# ir_serial_interface.net
KiCad netlist of a schematic drawn in EAGLE
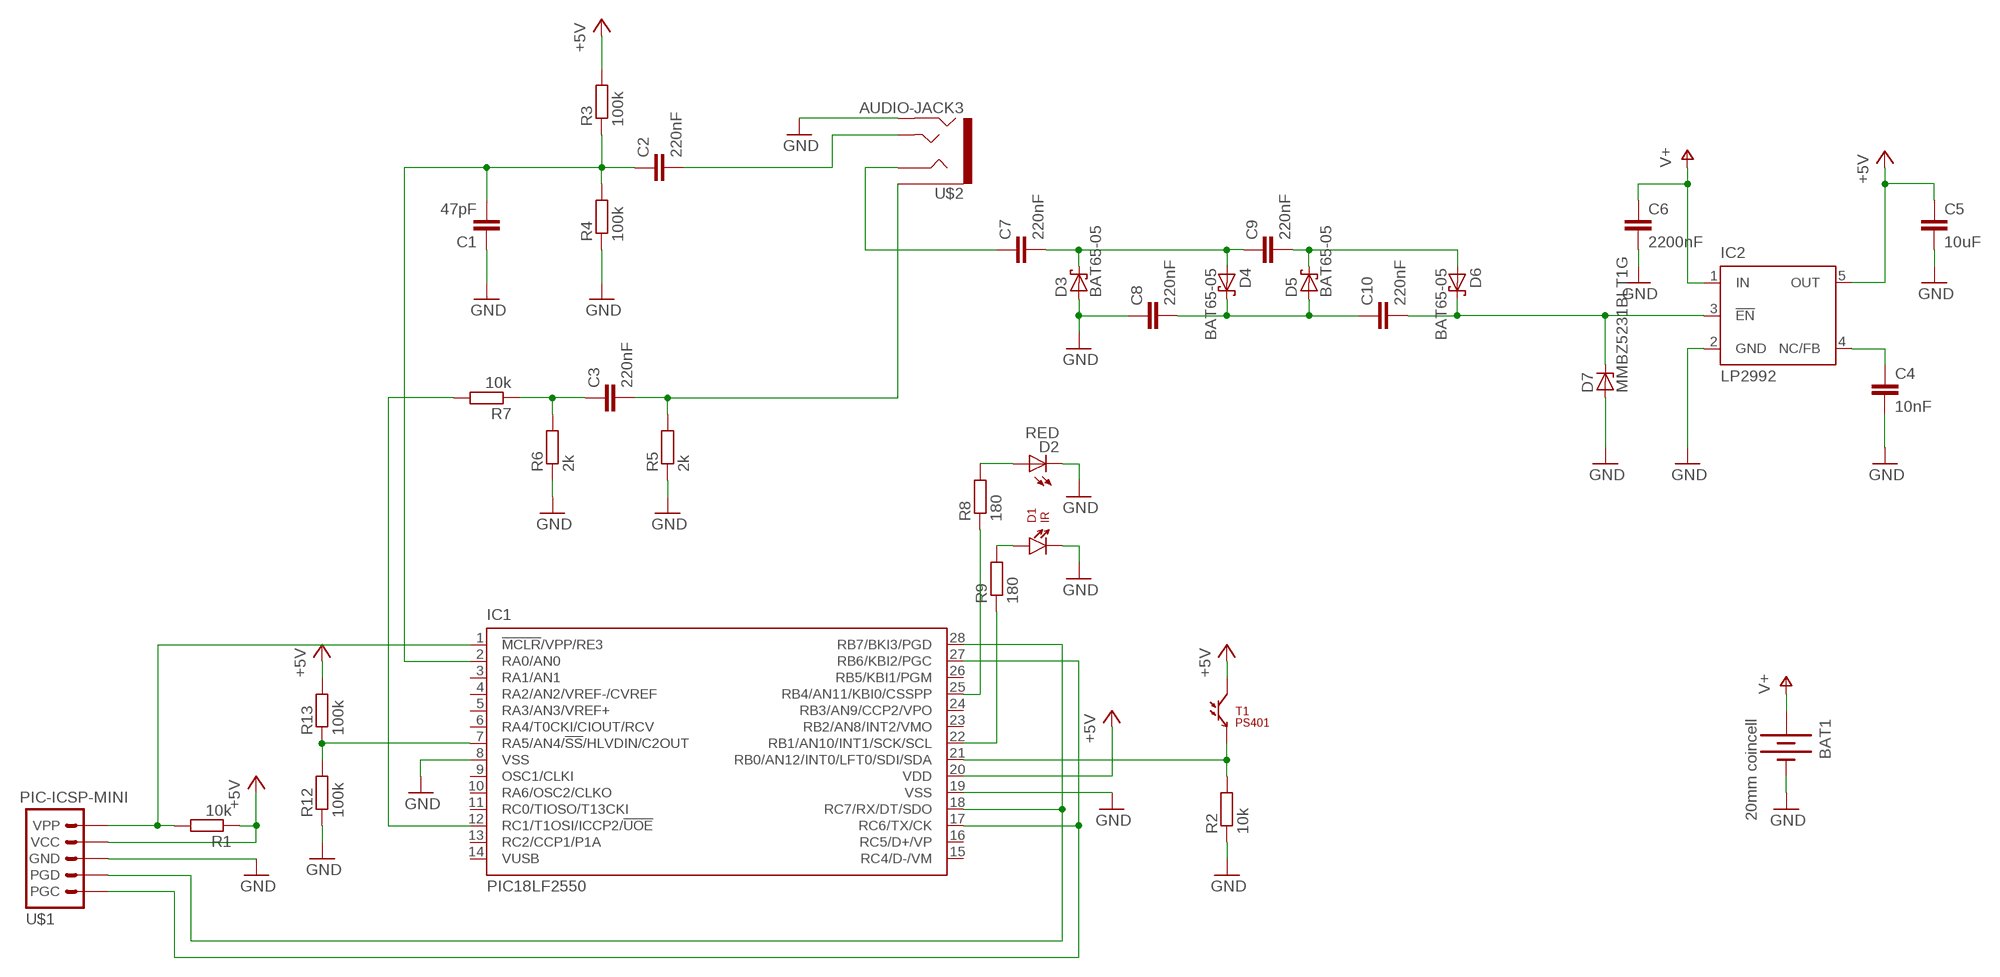
[diagram p0: schematic, sheet 1]

(export (version "E")
  (design (tool "Eeschema 10.0.6"))
  (components
    (comp (ref "BAT1")
      (value "20mm coincell")
      (footprint "eagle-import:BATTCOM_20MM_PTH")
      (libsource (lib "eagle-import") (part "BATTERY20PTH"))
    )
    (comp (ref "C1")
      (value "47pF")
      (footprint "eagle-import:0805")
      (libsource (lib "eagle-import") (part "CAP0805"))
    )
    (comp (ref "C2")
      (value "220nF")
      (footprint "eagle-import:0805")
      (libsource (lib "eagle-import") (part "CAP0805"))
    )
    (comp (ref "C3")
      (value "220nF")
      (footprint "eagle-import:0805")
      (libsource (lib "eagle-import") (part "CAP0805"))
    )
    (comp (ref "C4")
      (value "10nF")
      (footprint "eagle-import:C0805")
      (libsource (lib "eagle-import") (part "C-EUC0805"))
    )
    (comp (ref "C5")
      (value "10uF")
      (footprint "eagle-import:C0805")
      (libsource (lib "eagle-import") (part "C-EUC0805"))
    )
    (comp (ref "C6")
      (value "2200nF")
      (footprint "eagle-import:C0805")
      (libsource (lib "eagle-import") (part "C-EUC0805"))
    )
    (comp (ref "C7")
      (value "220nF")
      (footprint "eagle-import:C0805")
      (libsource (lib "eagle-import") (part "C-EUC0805"))
    )
    (comp (ref "C8")
      (value "220nF")
      (footprint "eagle-import:C0805")
      (libsource (lib "eagle-import") (part "C-EUC0805"))
    )
    (comp (ref "C9")
      (value "220nF")
      (footprint "eagle-import:C0805")
      (libsource (lib "eagle-import") (part "C-EUC0805"))
    )
    (comp (ref "C10")
      (value "220nF")
      (footprint "eagle-import:C0805")
      (libsource (lib "eagle-import") (part "C-EUC0805"))
    )
    (comp (ref "D1")
      (value "IR")
      (footprint "eagle-import:LTE-302")
      (libsource (lib "eagle-import") (part "LTE-302"))
    )
    (comp (ref "D2")
      (value "RED")
      (footprint "eagle-import:LED-1206")
      (libsource (lib "eagle-import") (part "LED-REDLILYPAD"))
    )
    (comp (ref "D3")
      (value "BAT65-05")
      (footprint "eagle-import:SOT23")
      (libsource (lib "eagle-import") (part "BAT54"))
    )
    (comp (ref "D4")
      (value "BAT65-05")
      (footprint "eagle-import:SOT23")
      (libsource (lib "eagle-import") (part "BAT54"))
    )
    (comp (ref "D5")
      (value "BAT65-05")
      (footprint "eagle-import:SOT23")
      (libsource (lib "eagle-import") (part "BAT54"))
    )
    (comp (ref "D6")
      (value "BAT65-05")
      (footprint "eagle-import:SOT23")
      (libsource (lib "eagle-import") (part "BAT54"))
    )
    (comp (ref "D7")
      (value "MMBZ5231BLT1G")
      (footprint "eagle-import:SOT23")
      (libsource (lib "eagle-import") (part "ZENER-DIODESOT23"))
    )
    (comp (ref "IC1")
      (value "PIC18LF2550")
      (footprint "eagle-import:SO28W")
      (fields (field (name "MF") "MICROCHIP") (field (name "MPN") "PIC18F2550-I/SO"))
      (libsource (lib "eagle-import") (part "PIC18F2_28W550"))
    )
    (comp (ref "IC2")
      (value "LP2992")
      (footprint "eagle-import:SOT23-DBV")
      (fields (field (name "MF") "TEXAS INSTRUMENTS") (field (name "MPN") "TPS77001DBVT"))
      (libsource (lib "eagle-import") (part "TPS77001"))
    )
    (comp (ref "R1")
      (value "10k")
      (footprint "eagle-import:M0805")
      (libsource (lib "eagle-import") (part "R-EU_M0805"))
    )
    (comp (ref "R2")
      (value "10k")
      (footprint "eagle-import:M0805")
      (libsource (lib "eagle-import") (part "R-EU_M0805"))
    )
    (comp (ref "R3")
      (value "100k")
      (footprint "eagle-import:M0805")
      (libsource (lib "eagle-import") (part "R-EU_M0805"))
    )
    (comp (ref "R4")
      (value "100k")
      (footprint "eagle-import:M0805")
      (libsource (lib "eagle-import") (part "R-EU_M0805"))
    )
    (comp (ref "R5")
      (value "2k")
      (footprint "eagle-import:M0805")
      (libsource (lib "eagle-import") (part "R-EU_M0805"))
    )
    (comp (ref "R6")
      (value "2k")
      (footprint "eagle-import:M0805")
      (libsource (lib "eagle-import") (part "R-EU_M0805"))
    )
    (comp (ref "R7")
      (value "10k")
      (footprint "eagle-import:M0805")
      (libsource (lib "eagle-import") (part "R-EU_M0805"))
    )
    (comp (ref "R8")
      (value "180")
      (footprint "eagle-import:M0805")
      (libsource (lib "eagle-import") (part "R-EU_M0805"))
    )
    (comp (ref "R9")
      (value "180")
      (footprint "eagle-import:M0805")
      (libsource (lib "eagle-import") (part "R-EU_M0805"))
    )
    (comp (ref "R12")
      (value "100k")
      (footprint "eagle-import:M0805")
      (libsource (lib "eagle-import") (part "R-EU_M0805"))
    )
    (comp (ref "R13")
      (value "100k")
      (footprint "eagle-import:M0805")
      (libsource (lib "eagle-import") (part "R-EU_M0805"))
    )
    (comp (ref "T1")
      (value "PS401")
      (footprint "eagle-import:LTR-301")
      (libsource (lib "eagle-import") (part "LTR-301"))
    )
    (comp (ref "U$1")
      (value "PIC-ICSP-MINI")
      (footprint "eagle-import:PIC-ICSP-MINI")
      (libsource (lib "eagle-import") (part "PIC-ICSP-MINI"))
    )
    (comp (ref "U$2")
      (value "AUDIO-JACK3")
      (footprint "eagle-import:AUDIO-JACK-TRRS-SMD")
      (libsource (lib "eagle-import") (part "AUDIO-JACK3"))
    )
  )
  (nets
    (net (code "1") (name "+5V") (class "Default")
      (node (ref "C5") (pin "1") (pinfunction "1_1") (pintype "passive"))
      (node (ref "IC1") (pin "20") (pinfunction "VDD_20") (pintype "power_in"))
      (node (ref "IC2") (pin "5") (pinfunction "OUT_5") (pintype "passive"))
      (node (ref "R1") (pin "1") (pinfunction "1_1") (pintype "passive"))
      (node (ref "R13") (pin "2") (pinfunction "2_2") (pintype "passive"))
      (node (ref "R3") (pin "2") (pinfunction "2_2") (pintype "passive"))
      (node (ref "T1") (pin "C") (pinfunction "C_C") (pintype "bidirectional"))
      (node (ref "U$1") (pin "2") (pinfunction "VCC_2") (pintype "passive"))
    )
    (net (code "2") (name "GND") (class "Default")
      (node (ref "BAT1") (pin "2") (pinfunction "-_2") (pintype "power_in"))
      (node (ref "C1") (pin "1") (pinfunction "1_1") (pintype "passive"))
      (node (ref "C4") (pin "2") (pinfunction "2_2") (pintype "passive"))
      (node (ref "C5") (pin "2") (pinfunction "2_2") (pintype "passive"))
      (node (ref "C6") (pin "2") (pinfunction "2_2") (pintype "passive"))
      (node (ref "C8") (pin "1") (pinfunction "1_1") (pintype "passive"))
      (node (ref "D1") (pin "C") (pinfunction "C_C") (pintype "bidirectional"))
      (node (ref "D2") (pin "C") (pinfunction "C_C") (pintype "passive"))
      (node (ref "D3") (pin "1") (pinfunction "A_1") (pintype "passive"))
      (node (ref "D7") (pin "1") (pinfunction "A_1") (pintype "passive"))
      (node (ref "IC1") (pin "19") (pinfunction "VSS_19") (pintype "power_in"))
      (node (ref "IC1") (pin "8") (pinfunction "VSS_8") (pintype "power_in"))
      (node (ref "IC2") (pin "2") (pinfunction "GND_2") (pintype "power_in"))
      (node (ref "R12") (pin "1") (pinfunction "1_1") (pintype "passive"))
      (node (ref "R2") (pin "1") (pinfunction "1_1") (pintype "passive"))
      (node (ref "R4") (pin "1") (pinfunction "1_1") (pintype "passive"))
      (node (ref "R5") (pin "1") (pinfunction "1_1") (pintype "passive"))
      (node (ref "R6") (pin "1") (pinfunction "1_1") (pintype "passive"))
      (node (ref "U$1") (pin "3") (pinfunction "GND_3") (pintype "passive"))
      (node (ref "U$2") (pin "RING2") (pinfunction "RING2_RING2") (pintype "bidirectional"))
    )
    (net (code "3") (name "Net-(C2-Pad2)") (class "Default")
      (node (ref "C2") (pin "2") (pinfunction "2_2") (pintype "passive"))
      (node (ref "U$2") (pin "TIP") (pinfunction "TIP_TIP") (pintype "bidirectional"))
    )
    (net (code "4") (name "Net-(C3-Pad1)") (class "Default")
      (node (ref "C3") (pin "1") (pinfunction "1_1") (pintype "passive"))
      (node (ref "R6") (pin "2") (pinfunction "2_2") (pintype "passive"))
      (node (ref "R7") (pin "1") (pinfunction "1_1") (pintype "passive"))
    )
    (net (code "5") (name "Net-(C3-Pad2)") (class "Default")
      (node (ref "C3") (pin "2") (pinfunction "2_2") (pintype "passive"))
      (node (ref "R5") (pin "2") (pinfunction "2_2") (pintype "passive"))
      (node (ref "U$2") (pin "EARTH") (pinfunction "EARTH_EARTH") (pintype "bidirectional"))
    )
    (net (code "6") (name "Net-(C7-Pad1)") (class "Default")
      (node (ref "C7") (pin "1") (pinfunction "1_1") (pintype "passive"))
      (node (ref "U$2") (pin "RING1") (pinfunction "RING1_RING1") (pintype "bidirectional"))
    )
    (net (code "7") (name "Net-(D1-PadA)") (class "Default")
      (node (ref "D1") (pin "A") (pinfunction "A_A") (pintype "bidirectional"))
      (node (ref "R9") (pin "2") (pinfunction "2_2") (pintype "passive"))
    )
    (net (code "8") (name "Net-(D2-PadA)") (class "Default")
      (node (ref "D2") (pin "A") (pinfunction "A_A") (pintype "passive"))
      (node (ref "R8") (pin "2") (pinfunction "2_2") (pintype "passive"))
    )
    (net (code "9") (name "Net-(D3-C)") (class "Default")
      (node (ref "C7") (pin "2") (pinfunction "2_2") (pintype "passive"))
      (node (ref "C9") (pin "1") (pinfunction "1_1") (pintype "passive"))
      (node (ref "D3") (pin "3") (pinfunction "C_3") (pintype "passive"))
      (node (ref "D4") (pin "1") (pinfunction "A_1") (pintype "passive"))
    )
    (net (code "10") (name "Net-(D4-C)") (class "Default")
      (node (ref "C10") (pin "1") (pinfunction "1_1") (pintype "passive"))
      (node (ref "C8") (pin "2") (pinfunction "2_2") (pintype "passive"))
      (node (ref "D4") (pin "3") (pinfunction "C_3") (pintype "passive"))
      (node (ref "D5") (pin "1") (pinfunction "A_1") (pintype "passive"))
    )
    (net (code "11") (name "Net-(D5-C)") (class "Default")
      (node (ref "C9") (pin "2") (pinfunction "2_2") (pintype "passive"))
      (node (ref "D5") (pin "3") (pinfunction "C_3") (pintype "passive"))
      (node (ref "D6") (pin "1") (pinfunction "A_1") (pintype "passive"))
    )
    (net (code "12") (name "Net-(D6-C)") (class "Default")
      (node (ref "C10") (pin "2") (pinfunction "2_2") (pintype "passive"))
      (node (ref "D6") (pin "3") (pinfunction "C_3") (pintype "passive"))
      (node (ref "D7") (pin "3") (pinfunction "C_3") (pintype "passive"))
      (node (ref "IC2") (pin "3") (pinfunction "~{EN}_3") (pintype "input"))
    )
    (net (code "13") (name "Net-(IC1-RA0{slash}AN0)") (class "Default")
      (node (ref "C1") (pin "2") (pinfunction "2_2") (pintype "passive"))
      (node (ref "C2") (pin "1") (pinfunction "1_1") (pintype "passive"))
      (node (ref "IC1") (pin "2") (pinfunction "RA0/AN0_2") (pintype "bidirectional"))
      (node (ref "R3") (pin "1") (pinfunction "1_1") (pintype "passive"))
      (node (ref "R4") (pin "2") (pinfunction "2_2") (pintype "passive"))
    )
    (net (code "14") (name "Net-(IC1-RA5{slash}AN4{slash}~{SS}{slash}HLVDIN{slash}C2OUT)") (class "Default")
      (node (ref "IC1") (pin "7") (pinfunction "RA5/AN4/~{SS}/HLVDIN/C2OUT_7") (pintype "bidirectional"))
      (node (ref "R12") (pin "2") (pinfunction "2_2") (pintype "passive"))
      (node (ref "R13") (pin "1") (pinfunction "1_1") (pintype "passive"))
    )
    (net (code "15") (name "Net-(IC1-RB0{slash}AN12{slash}INT0{slash}LFT0{slash}SDI{slash}SDA)") (class "Default")
      (node (ref "IC1") (pin "21") (pinfunction "RB0/AN12/INT0/LFT0/SDI/SDA_21") (pintype "bidirectional"))
      (node (ref "R2") (pin "2") (pinfunction "2_2") (pintype "passive"))
      (node (ref "T1") (pin "E") (pinfunction "E_E") (pintype "bidirectional"))
    )
    (net (code "16") (name "Net-(IC1-RB1{slash}AN10{slash}INT1{slash}SCK{slash}SCL)") (class "Default")
      (node (ref "IC1") (pin "22") (pinfunction "RB1/AN10/INT1/SCK/SCL_22") (pintype "bidirectional"))
      (node (ref "R9") (pin "1") (pinfunction "1_1") (pintype "passive"))
    )
    (net (code "17") (name "Net-(IC1-RB4{slash}AN11{slash}KBI0{slash}CSSPP)") (class "Default")
      (node (ref "IC1") (pin "25") (pinfunction "RB4/AN11/KBI0/CSSPP_25") (pintype "bidirectional"))
      (node (ref "R8") (pin "1") (pinfunction "1_1") (pintype "passive"))
    )
    (net (code "18") (name "Net-(IC1-RB6{slash}KBI2{slash}PGC)") (class "Default")
      (node (ref "IC1") (pin "17") (pinfunction "RC6/TX/CK_17") (pintype "bidirectional"))
      (node (ref "IC1") (pin "27") (pinfunction "RB6/KBI2/PGC_27") (pintype "bidirectional"))
      (node (ref "U$1") (pin "5") (pinfunction "PGC_5") (pintype "passive"))
    )
    (net (code "19") (name "Net-(IC1-RB7{slash}BKI3{slash}PGD)") (class "Default")
      (node (ref "IC1") (pin "18") (pinfunction "RC7/RX/DT/SDO_18") (pintype "bidirectional"))
      (node (ref "IC1") (pin "28") (pinfunction "RB7/BKI3/PGD_28") (pintype "bidirectional"))
      (node (ref "U$1") (pin "4") (pinfunction "PGD_4") (pintype "passive"))
    )
    (net (code "20") (name "Net-(IC1-RC1{slash}T1OSI{slash}ICCP2{slash}~{UOE})") (class "Default")
      (node (ref "IC1") (pin "12") (pinfunction "RC1/T1OSI/ICCP2/~{UOE}_12") (pintype "bidirectional"))
      (node (ref "R7") (pin "2") (pinfunction "2_2") (pintype "passive"))
    )
    (net (code "21") (name "Net-(IC1-~{MCLR}{slash}VPP{slash}RE3)") (class "Default")
      (node (ref "IC1") (pin "1") (pinfunction "~{MCLR}/VPP/RE3_1") (pintype "input"))
      (node (ref "R1") (pin "2") (pinfunction "2_2") (pintype "passive"))
      (node (ref "U$1") (pin "1") (pinfunction "VPP_1") (pintype "passive"))
    )
    (net (code "22") (name "Net-(IC2-NC{slash}FB)") (class "Default")
      (node (ref "C4") (pin "1") (pinfunction "1_1") (pintype "passive"))
      (node (ref "IC2") (pin "4") (pinfunction "NC/FB_4") (pintype "passive"))
    )
    (net (code "23") (name "V+") (class "Default")
      (node (ref "BAT1") (pin "1") (pinfunction "+_1") (pintype "power_in"))
      (node (ref "C6") (pin "1") (pinfunction "1_1") (pintype "passive"))
      (node (ref "IC2") (pin "1") (pinfunction "IN_1") (pintype "input"))
    )
    (net (code "24") (name "unconnected-(IC1-OSC1{slash}CLKI-Pad9)") (class "Default")
      (node (ref "IC1") (pin "9") (pinfunction "OSC1/CLKI_9") (pintype "input"))
    )
    (net (code "25") (name "unconnected-(IC1-RA1{slash}AN1-Pad3)") (class "Default")
      (node (ref "IC1") (pin "3") (pinfunction "RA1/AN1_3") (pintype "bidirectional"))
    )
    (net (code "26") (name "unconnected-(IC1-RA2{slash}AN2{slash}VREF-{slash}CVREF-Pad4)") (class "Default")
      (node (ref "IC1") (pin "4") (pinfunction "RA2/AN2/VREF-/CVREF_4") (pintype "bidirectional"))
    )
    (net (code "27") (name "unconnected-(IC1-RA3{slash}AN3{slash}VREF+-Pad5)") (class "Default")
      (node (ref "IC1") (pin "5") (pinfunction "RA3/AN3/VREF+_5") (pintype "bidirectional"))
    )
    (net (code "28") (name "unconnected-(IC1-RA4{slash}T0CKI{slash}CIOUT{slash}RCV-Pad6)") (class "Default")
      (node (ref "IC1") (pin "6") (pinfunction "RA4/T0CKI/CIOUT/RCV_6") (pintype "bidirectional"))
    )
    (net (code "29") (name "unconnected-(IC1-RA6{slash}OSC2{slash}CLKO-Pad10)") (class "Default")
      (node (ref "IC1") (pin "10") (pinfunction "RA6/OSC2/CLKO_10") (pintype "output"))
    )
    (net (code "30") (name "unconnected-(IC1-RB2{slash}AN8{slash}INT2{slash}VMO-Pad23)") (class "Default")
      (node (ref "IC1") (pin "23") (pinfunction "RB2/AN8/INT2/VMO_23") (pintype "bidirectional"))
    )
    (net (code "31") (name "unconnected-(IC1-RB3{slash}AN9{slash}CCP2{slash}VPO-Pad24)") (class "Default")
      (node (ref "IC1") (pin "24") (pinfunction "RB3/AN9/CCP2/VPO_24") (pintype "bidirectional"))
    )
    (net (code "32") (name "unconnected-(IC1-RB5{slash}KBI1{slash}PGM-Pad26)") (class "Default")
      (node (ref "IC1") (pin "26") (pinfunction "RB5/KBI1/PGM_26") (pintype "bidirectional"))
    )
    (net (code "33") (name "unconnected-(IC1-RC0{slash}TIOSO{slash}T13CKI-Pad11)") (class "Default")
      (node (ref "IC1") (pin "11") (pinfunction "RC0/TIOSO/T13CKI_11") (pintype "bidirectional"))
    )
    (net (code "34") (name "unconnected-(IC1-RC2{slash}CCP1{slash}P1A-Pad13)") (class "Default")
      (node (ref "IC1") (pin "13") (pinfunction "RC2/CCP1/P1A_13") (pintype "bidirectional"))
    )
    (net (code "35") (name "unconnected-(IC1-RC4{slash}D-{slash}VM-Pad15)") (class "Default")
      (node (ref "IC1") (pin "15") (pinfunction "RC4/D-/VM_15") (pintype "bidirectional"))
    )
    (net (code "36") (name "unconnected-(IC1-RC5{slash}D+{slash}VP-Pad16)") (class "Default")
      (node (ref "IC1") (pin "16") (pinfunction "RC5/D+/VP_16") (pintype "bidirectional"))
    )
    (net (code "37") (name "unconnected-(IC1-VUSB-Pad14)") (class "Default")
      (node (ref "IC1") (pin "14") (pinfunction "VUSB_14") (pintype "bidirectional"))
    )
  )
)
